# TRS_Jack_Breakout.net
KiCad netlist of a schematic drawn in EAGLE
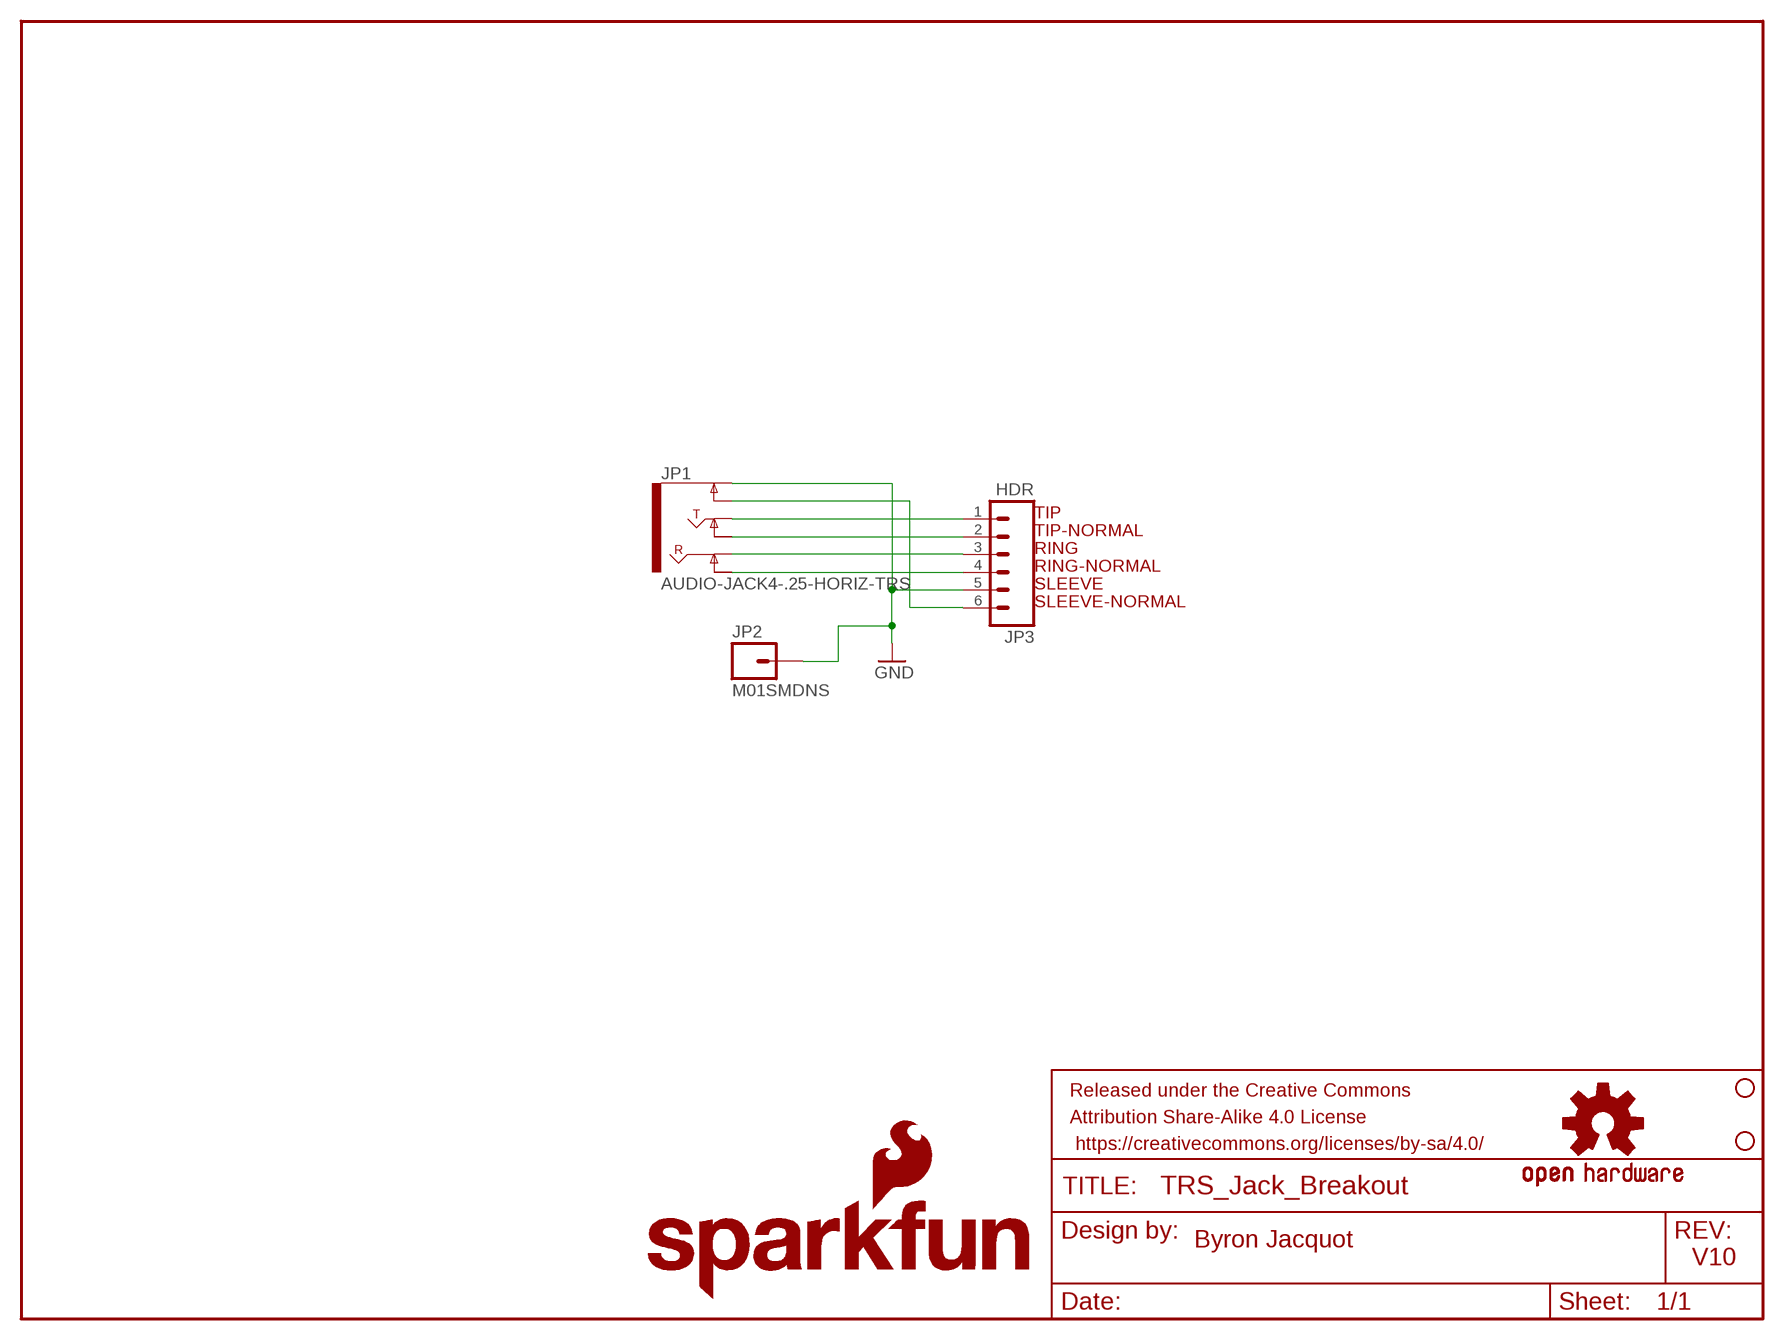
[diagram p0: schematic, sheet 1]

(export (version "E")
  (design (tool "Eeschema 10.0.6"))
  (components
    (comp (ref "FRAME1")
      (value "FRAME-LETTER")
      (footprint "eagle-import:CREATIVE_COMMONS")
      (libsource (lib "eagle-import") (part "FRAME-LETTER"))
    )
    (comp (ref "JP1")
      (value "AUDIO-JACK4-.25-HORIZ-TRS")
      (footprint "eagle-import:AUDIO-JACK-.25-INCH-HORIZ-PTH")
      (libsource (lib "eagle-import") (part "AUDIO-JACK4-.25-HORIZ-TRS"))
    )
    (comp (ref "JP2")
      (value "M01SMDNS")
      (footprint "eagle-import:1X01NS")
      (libsource (lib "eagle-import") (part "M01SMDNS"))
    )
    (comp (ref "JP3")
      (value "HDR")
      (footprint "eagle-import:1X06_NO_SILK")
      (libsource (lib "eagle-import") (part "M06NO_SILK"))
    )
    (comp (ref "LOGO1")
      (value "SFE_LOGO_NAME_FLAME.1_INCH")
      (footprint "eagle-import:SFE_LOGO_NAME_FLAME_.1")
      (libsource (lib "eagle-import") (part "SFE_LOGO_NAME_FLAME.1_INCH"))
    )
    (comp (ref "LOGO2")
      (value "OSHW-LOGOS")
      (footprint "eagle-import:OSHW-LOGO-S")
      (libsource (lib "eagle-import") (part "OSHW-LOGOS"))
    )
    (comp (ref "STANDOFF1")
      (value "STAND-OFF")
      (footprint "eagle-import:STAND-OFF")
      (libsource (lib "eagle-import") (part "STAND-OFF"))
    )
    (comp (ref "STANDOFF2")
      (value "STAND-OFF")
      (footprint "eagle-import:STAND-OFF")
      (libsource (lib "eagle-import") (part "STAND-OFF"))
    )
  )
  (nets
    (net (code "1") (name "GND") (class "Default")
      (node (ref "JP1") (pin "SLEEVE") (pinfunction "EARTH_SLEEVE") (pintype "bidirectional"))
      (node (ref "JP2") (pin "1") (pinfunction "1_1") (pintype "passive"))
      (node (ref "JP3") (pin "5") (pinfunction "5_5") (pintype "passive"))
    )
    (net (code "2") (name "Net-(JP1-EARTH-NORM)") (class "Default")
      (node (ref "JP1") (pin "SLEEVE-NORM") (pinfunction "EARTH-NORM_SLEEVE-NORM") (pintype "bidirectional"))
      (node (ref "JP3") (pin "6") (pinfunction "6_6") (pintype "passive"))
    )
    (net (code "3") (name "Net-(JP1-PadRING)") (class "Default")
      (node (ref "JP1") (pin "RING") (pinfunction "RING_RING") (pintype "bidirectional"))
      (node (ref "JP3") (pin "3") (pinfunction "3_3") (pintype "passive"))
    )
    (net (code "4") (name "Net-(JP1-PadRING-NORM)") (class "Default")
      (node (ref "JP1") (pin "RING-NORM") (pinfunction "RING-NORM_RING-NORM") (pintype "bidirectional"))
      (node (ref "JP3") (pin "4") (pinfunction "4_4") (pintype "passive"))
    )
    (net (code "5") (name "Net-(JP1-PadTIP)") (class "Default")
      (node (ref "JP1") (pin "TIP") (pinfunction "TIP_TIP") (pintype "bidirectional"))
      (node (ref "JP3") (pin "1") (pinfunction "1_1") (pintype "passive"))
    )
    (net (code "6") (name "Net-(JP1-PadTIP-NORM)") (class "Default")
      (node (ref "JP1") (pin "TIP-NORM") (pinfunction "TIP-NORM_TIP-NORM") (pintype "bidirectional"))
      (node (ref "JP3") (pin "2") (pinfunction "2_2") (pintype "passive"))
    )
  )
)
